# ch340e.net
KiCad netlist of a schematic drawn in Altium Designer
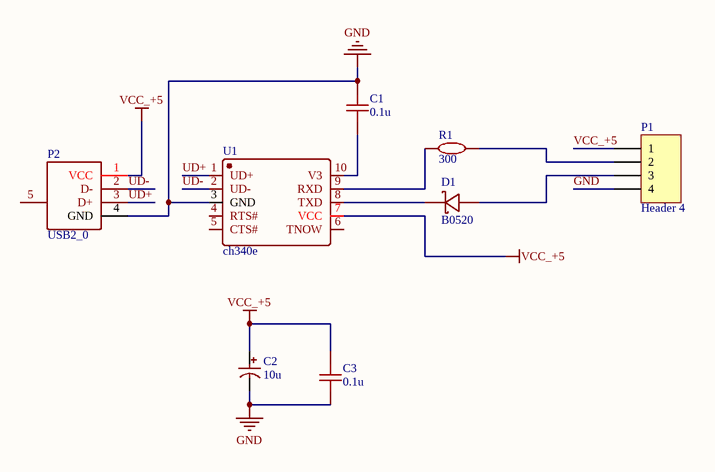
[diagram p0: ch340e.SchDoc]

(export (version "E")
  (design (tool "Eeschema 10.0.6"))
  (components
    (comp (ref "C1") (value "0.1u") (footprint "0805_C") (libsource (lib "Schlib1") (part "0805_C0.1uf")))
    (comp (ref "C2") (value "10u") (footprint "SMD8x10.2") (libsource (lib "Schlib1") (part "SMD8x10.2")))
    (comp (ref "C3") (value "0.1u") (footprint "0805_C") (libsource (lib "Schlib1") (part "0805_C0.1uf")))
    (comp (ref "D1") (value "B0520") (footprint "B0520") (libsource (lib "Schlib1") (part "B0520")))
    (comp (ref "P1")
      (value "Header 4")
      (footprint "HDR1X4")
      (description "Header, 4-Pin")
      (fields (field (name "PUBLISHER") "Altium Limited"))
      (libsource (lib "Miscellaneous Connectors") (part "Header 4"))
    )
    (comp (ref "P2") (value "USB2_0") (footprint "USB2_0") (libsource (lib "Schlib1") (part "USB2_0")))
    (comp (ref "R1") (value "300") (footprint "0805_R") (libsource (lib "Schlib1") (part "0805_R300")))
    (comp (ref "U1") (value "ch340e") (footprint "CH340E") (libsource (lib "Schlib1") (part "ch340")))
  )
  (nets
    (net (code "1") (name "/UD+") (class "Default")
      (node (ref "P2") (pin "3") (pinfunction "D+_3") (pintype "passive"))
      (node (ref "U1") (pin "1") (pinfunction "UD+_1") (pintype "passive"))
    )
    (net (code "2") (name "/UD-") (class "Default")
      (node (ref "P2") (pin "2") (pinfunction "D-_2") (pintype "passive"))
      (node (ref "U1") (pin "2") (pinfunction "UD-_2") (pintype "passive"))
    )
    (net (code "3") (name "GND") (class "Default")
      (node (ref "C1") (pin "2") (pinfunction "2_2") (pintype "passive"))
      (node (ref "C2") (pin "2") (pinfunction "2_2") (pintype "passive"))
      (node (ref "C3") (pin "1") (pinfunction "1_1") (pintype "passive"))
      (node (ref "P1") (pin "4") (pinfunction "4_4") (pintype "passive"))
      (node (ref "P2") (pin "4") (pinfunction "GND_4") (pintype "passive"))
      (node (ref "U1") (pin "3") (pinfunction "GND_3") (pintype "passive"))
    )
    (net (code "4") (name "Net-(D1-A)") (class "Default")
      (node (ref "D1") (pin "2") (pinfunction "A_2") (pintype "passive"))
      (node (ref "P1") (pin "3") (pinfunction "3_3") (pintype "passive"))
    )
    (net (code "5") (name "Net-(D1-C)") (class "Default")
      (node (ref "D1") (pin "1") (pinfunction "C_1") (pintype "passive"))
      (node (ref "U1") (pin "8") (pinfunction "TXD_8") (pintype "passive"))
    )
    (net (code "6") (name "Net-(P1-Pad2)") (class "Default")
      (node (ref "P1") (pin "2") (pinfunction "2_2") (pintype "passive"))
      (node (ref "R1") (pin "2") (pinfunction "2_2") (pintype "passive"))
    )
    (net (code "7") (name "Net-(U1-RXD)") (class "Default")
      (node (ref "R1") (pin "1") (pinfunction "1_1") (pintype "passive"))
      (node (ref "U1") (pin "9") (pinfunction "RXD_9") (pintype "passive"))
    )
    (net (code "8") (name "Net-(U1-V3)") (class "Default")
      (node (ref "C1") (pin "1") (pinfunction "1_1") (pintype "passive"))
      (node (ref "U1") (pin "10") (pinfunction "V3_10") (pintype "passive"))
    )
    (net (code "9") (name "VCC_+5") (class "Default")
      (node (ref "C2") (pin "1") (pinfunction "1_1") (pintype "passive"))
      (node (ref "C3") (pin "2") (pinfunction "2_2") (pintype "passive"))
      (node (ref "P1") (pin "1") (pinfunction "1_1") (pintype "passive"))
      (node (ref "P2") (pin "1") (pinfunction "VCC_1") (pintype "passive"))
      (node (ref "U1") (pin "7") (pinfunction "VCC_7") (pintype "passive"))
    )
    (net (code "10") (name "unconnected-(P2-SH1-Pad5)") (class "Default")
      (node (ref "P2") (pin "5") (pinfunction "SH1_5") (pintype "passive"))
    )
    (net (code "11") (name "unconnected-(U1-CTS#-Pad5)") (class "Default")
      (node (ref "U1") (pin "5") (pinfunction "CTS#_5") (pintype "passive"))
    )
    (net (code "12") (name "unconnected-(U1-RTS#-Pad4)") (class "Default")
      (node (ref "U1") (pin "4") (pinfunction "RTS#_4") (pintype "passive"))
    )
    (net (code "13") (name "unconnected-(U1-TNOW-Pad6)") (class "Default")
      (node (ref "U1") (pin "6") (pinfunction "TNOW_6") (pintype "passive"))
    )
  )
)
